# test_board.net
KiCad netlist of a schematic drawn in EAGLE
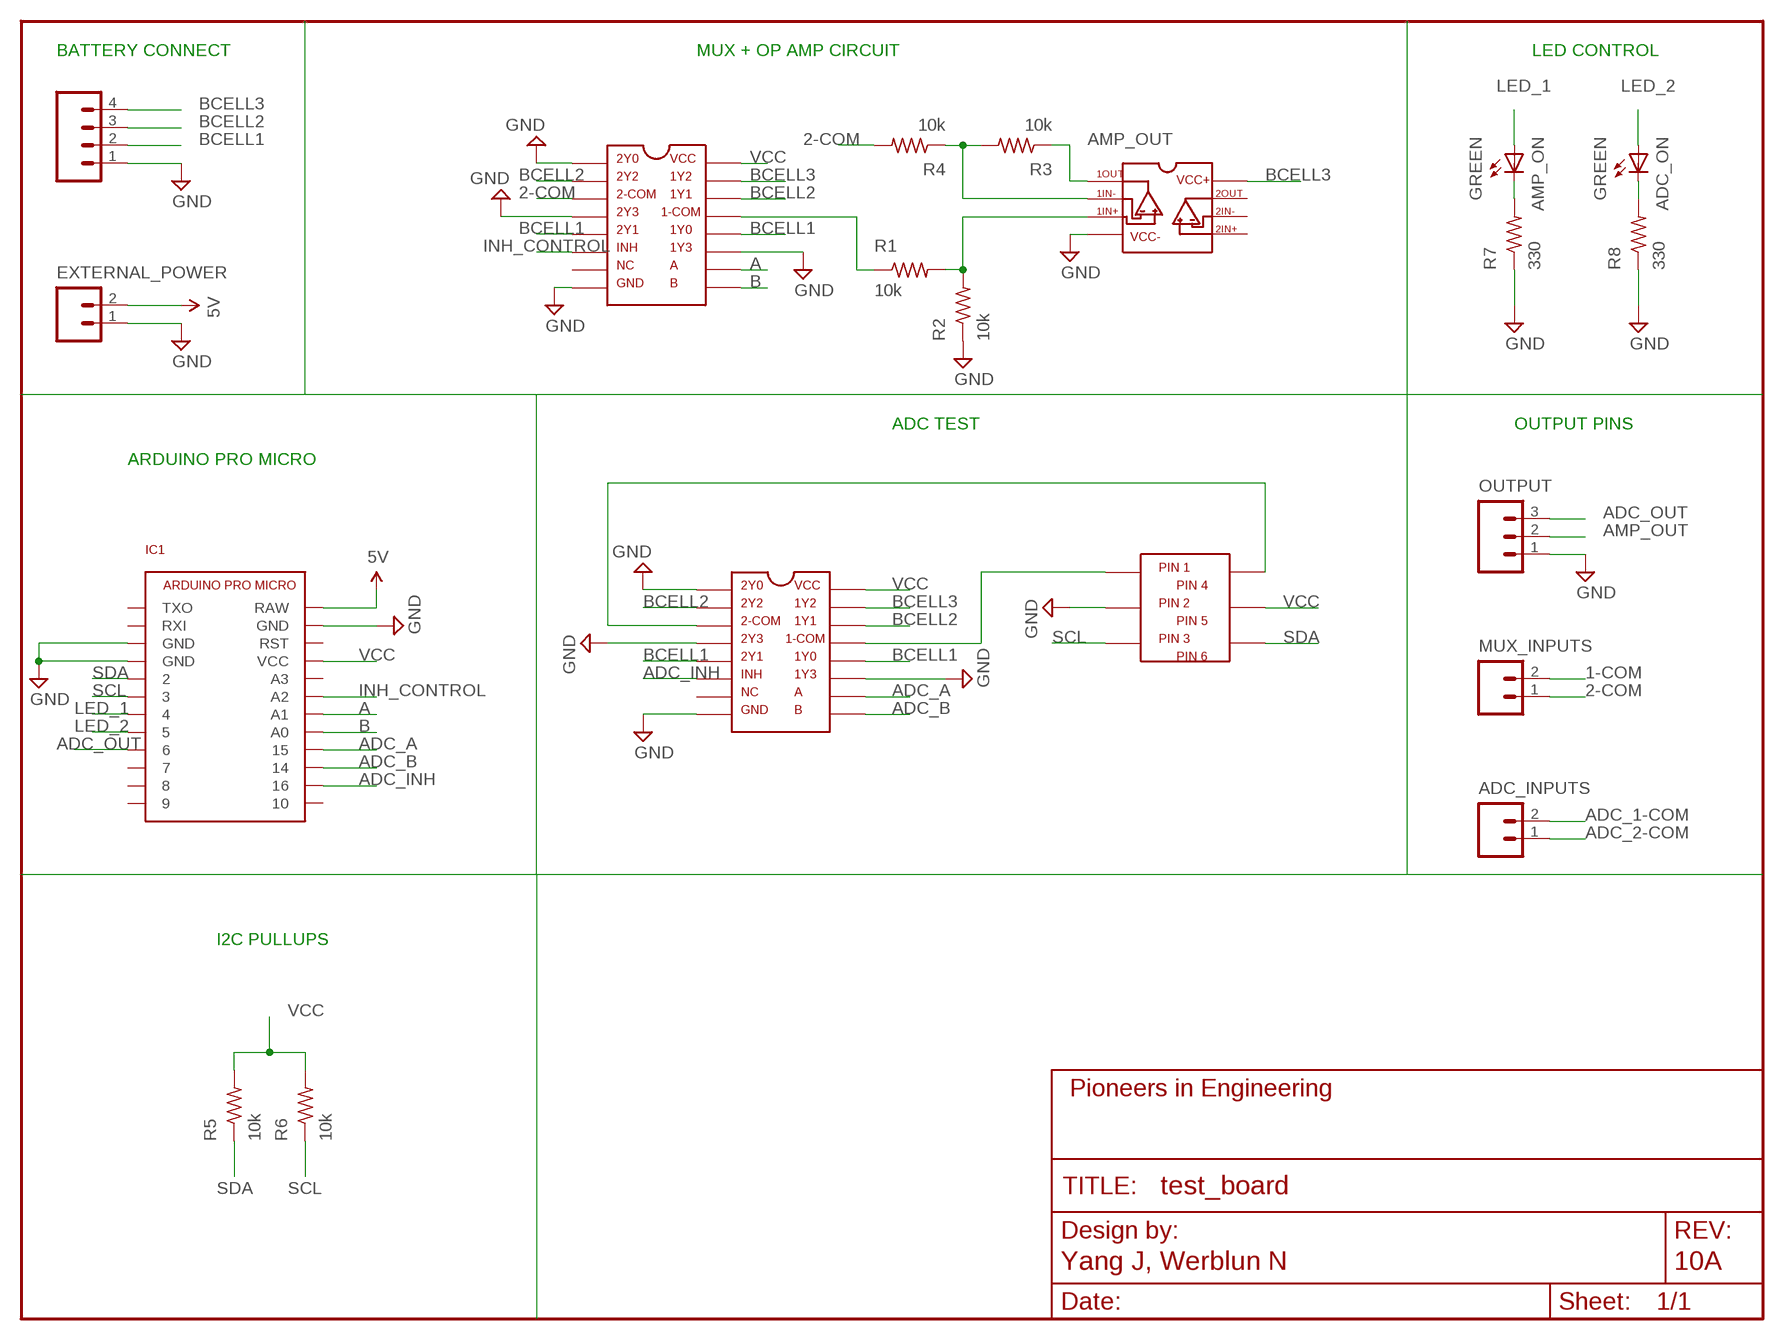
[diagram p0: schematic, sheet 1]

(export (version "E")
  (design (tool "Eeschema 10.0.6"))
  (components
    (comp (ref "ADC_INPUTS")
      (value "M02PTH")
      (footprint "eagle-import:1X02")
      (libsource (lib "eagle-import") (part "M02PTH"))
    )
    (comp (ref "ADC_ON")
      (value "GREEN")
      (footprint "eagle-import:LED-0603")
      (fields
        (field (name "DISTRIBUTOR_PART_NUMBER") "160-1415-1-ND")
        (field (name "MANUFACTURER") "Lite-On Inc")
        (field (name "MANUFACTURER_PART_NUMBER") "LTST-C170KRKT")
      )
      (libsource (lib "eagle-import") (part "LED0603"))
    )
    (comp (ref "AMP_ON")
      (value "GREEN")
      (footprint "eagle-import:LED-0603")
      (fields
        (field (name "DISTRIBUTOR_PART_NUMBER") "160-1415-1-ND")
        (field (name "MANUFACTURER") "Lite-On Inc")
        (field (name "MANUFACTURER_PART_NUMBER") "LTST-C170KRKT")
      )
      (libsource (lib "eagle-import") (part "LED0603"))
    )
    (comp (ref "BATTERY_CONNECT")
      (value "XH_CONNECTOR_4POS")
      (footprint "eagle-import:XH_CONNECTOR_4POS_2.5MM")
      (libsource (lib "eagle-import") (part "XH_CONNECTOR_4POS"))
    )
    (comp (ref "EXTERNAL_POWER")
      (value "M02PTH")
      (footprint "eagle-import:1X02")
      (libsource (lib "eagle-import") (part "M02PTH"))
    )
    (comp (ref "IC1")
      (value "ARDUINO_PRO_MICRO")
      (footprint "eagle-import:ARDUINO_PRO_MICRO")
      (fields
        (field (name "DISTRIBUTOR_PART_NUMBER") "32284746884")
        (field (name "MANUFACTURER") "Feiyang electronics")
      )
      (libsource (lib "eagle-import") (part "ARDUINO_PRO_MICRO"))
    )
    (comp (ref "MUX_INPUTS")
      (value "M02PTH")
      (footprint "eagle-import:1X02")
      (libsource (lib "eagle-import") (part "M02PTH"))
    )
    (comp (ref "OUTPUT")
      (value "M03PTH")
      (footprint "eagle-import:1X03")
      (libsource (lib "eagle-import") (part "M03PTH"))
    )
    (comp (ref "R1")
      (value "10k")
      (footprint "eagle-import:R0603")
      (fields (field (name "MANUFACTURER") "Rohm Semiconductor"))
      (libsource (lib "eagle-import") (part "R-US_R0603"))
    )
    (comp (ref "R2")
      (value "10k")
      (footprint "eagle-import:R0603")
      (fields (field (name "MANUFACTURER") "Rohm Semiconductor"))
      (libsource (lib "eagle-import") (part "R-US_R0603"))
    )
    (comp (ref "R3")
      (value "10k")
      (footprint "eagle-import:R0603")
      (fields (field (name "MANUFACTURER") "Rohm Semiconductor"))
      (libsource (lib "eagle-import") (part "R-US_R0603"))
    )
    (comp (ref "R4")
      (value "10k")
      (footprint "eagle-import:R0603")
      (fields (field (name "MANUFACTURER") "Rohm Semiconductor"))
      (libsource (lib "eagle-import") (part "R-US_R0603"))
    )
    (comp (ref "R5")
      (value "10k")
      (footprint "eagle-import:R0603")
      (fields (field (name "MANUFACTURER") "Rohm Semiconductor"))
      (libsource (lib "eagle-import") (part "R-US_R0603"))
    )
    (comp (ref "R6")
      (value "10k")
      (footprint "eagle-import:R0603")
      (fields (field (name "MANUFACTURER") "Rohm Semiconductor"))
      (libsource (lib "eagle-import") (part "R-US_R0603"))
    )
    (comp (ref "R7")
      (value "330")
      (footprint "eagle-import:R0603")
      (fields (field (name "MANUFACTURER") "Rohm Semiconductor"))
      (libsource (lib "eagle-import") (part "R-US_R0603"))
    )
    (comp (ref "R8")
      (value "330")
      (footprint "eagle-import:R0603")
      (fields (field (name "MANUFACTURER") "Rohm Semiconductor"))
      (libsource (lib "eagle-import") (part "R-US_R0603"))
    )
    (comp (ref "U$1")
      (value "SN74HC4852")
      (footprint "eagle-import:DIL16")
      (libsource (lib "eagle-import") (part "SN74HC4852"))
    )
    (comp (ref "U$2")
      (value "TL072")
      (footprint "eagle-import:DIL08")
      (libsource (lib "eagle-import") (part "TL072"))
    )
    (comp (ref "U$3")
      (value "SOT-23_6PIN")
      (footprint "eagle-import:SOT-23_6PIN")
      (libsource (lib "eagle-import") (part "SOT-23_6PIN"))
    )
    (comp (ref "U$5")
      (value "SN74HC4852")
      (footprint "eagle-import:DIL16")
      (libsource (lib "eagle-import") (part "SN74HC4852"))
    )
  )
  (nets
    (net (code "1") (name "/1-COM") (class "Default")
      (node (ref "MUX_INPUTS") (pin "2") (pinfunction "2_2") (pintype "passive"))
      (node (ref "R1") (pin "1") (pinfunction "1_1") (pintype "passive"))
      (node (ref "U$1") (pin "13") (pinfunction "1-COM_13") (pintype "bidirectional"))
    )
    (net (code "2") (name "/2-COM") (class "Default")
      (node (ref "MUX_INPUTS") (pin "1") (pinfunction "1_1") (pintype "passive"))
      (node (ref "R4") (pin "2") (pinfunction "2_2") (pintype "passive"))
      (node (ref "U$1") (pin "3") (pinfunction "2-COM_3") (pintype "bidirectional"))
    )
    (net (code "3") (name "/A") (class "Default")
      (node (ref "IC1") (pin "A1") (pinfunction "A1_A1") (pintype "bidirectional"))
      (node (ref "U$1") (pin "10") (pinfunction "A_10") (pintype "bidirectional"))
    )
    (net (code "4") (name "/ADC_1-COM") (class "Default")
      (node (ref "ADC_INPUTS") (pin "2") (pinfunction "2_2") (pintype "passive"))
      (node (ref "U$3") (pin "P$1") (pinfunction "P$1_P$1") (pintype "bidirectional"))
      (node (ref "U$5") (pin "13") (pinfunction "1-COM_13") (pintype "bidirectional"))
    )
    (net (code "5") (name "/ADC_2-COM") (class "Default")
      (node (ref "ADC_INPUTS") (pin "1") (pinfunction "1_1") (pintype "passive"))
      (node (ref "U$3") (pin "P$4") (pinfunction "P$4_P$4") (pintype "bidirectional"))
      (node (ref "U$5") (pin "3") (pinfunction "2-COM_3") (pintype "bidirectional"))
    )
    (net (code "6") (name "/ADC_A") (class "Default")
      (node (ref "IC1") (pin "15") (pinfunction "15_15") (pintype "bidirectional"))
      (node (ref "U$5") (pin "10") (pinfunction "A_10") (pintype "bidirectional"))
    )
    (net (code "7") (name "/ADC_B") (class "Default")
      (node (ref "IC1") (pin "14") (pinfunction "14_14") (pintype "bidirectional"))
      (node (ref "U$5") (pin "9") (pinfunction "B_9") (pintype "bidirectional"))
    )
    (net (code "8") (name "/ADC_INH") (class "Default")
      (node (ref "IC1") (pin "16") (pinfunction "16_16") (pintype "bidirectional"))
      (node (ref "U$5") (pin "6") (pinfunction "INH_6") (pintype "bidirectional"))
    )
    (net (code "9") (name "/ADC_OUT") (class "Default")
      (node (ref "IC1") (pin "6") (pinfunction "6_6") (pintype "bidirectional"))
      (node (ref "OUTPUT") (pin "3") (pinfunction "3_3") (pintype "passive"))
    )
    (net (code "10") (name "/AMP_OUT") (class "Default")
      (node (ref "OUTPUT") (pin "2") (pinfunction "2_2") (pintype "passive"))
      (node (ref "R3") (pin "1") (pinfunction "1_1") (pintype "passive"))
      (node (ref "U$2") (pin "1") (pinfunction "1OUT_1") (pintype "bidirectional"))
    )
    (net (code "11") (name "/B") (class "Default")
      (node (ref "IC1") (pin "A0") (pinfunction "A0_A0") (pintype "bidirectional"))
      (node (ref "U$1") (pin "9") (pinfunction "B_9") (pintype "bidirectional"))
    )
    (net (code "12") (name "/BCELL1") (class "Default")
      (node (ref "BATTERY_CONNECT") (pin "2") (pinfunction "2_2") (pintype "passive"))
      (node (ref "U$1") (pin "12") (pinfunction "1Y0_12") (pintype "bidirectional"))
      (node (ref "U$1") (pin "5") (pinfunction "2Y1_5") (pintype "bidirectional"))
      (node (ref "U$5") (pin "12") (pinfunction "1Y0_12") (pintype "bidirectional"))
      (node (ref "U$5") (pin "5") (pinfunction "2Y1_5") (pintype "bidirectional"))
    )
    (net (code "13") (name "/BCELL2") (class "Default")
      (node (ref "BATTERY_CONNECT") (pin "3") (pinfunction "3_3") (pintype "passive"))
      (node (ref "U$1") (pin "14") (pinfunction "1Y1_14") (pintype "bidirectional"))
      (node (ref "U$1") (pin "2") (pinfunction "2Y2_2") (pintype "bidirectional"))
      (node (ref "U$5") (pin "14") (pinfunction "1Y1_14") (pintype "bidirectional"))
      (node (ref "U$5") (pin "2") (pinfunction "2Y2_2") (pintype "bidirectional"))
    )
    (net (code "14") (name "/BCELL3") (class "Default")
      (node (ref "BATTERY_CONNECT") (pin "4") (pinfunction "4_4") (pintype "passive"))
      (node (ref "U$1") (pin "15") (pinfunction "1Y2_15") (pintype "bidirectional"))
      (node (ref "U$2") (pin "8") (pinfunction "VCC+_8") (pintype "bidirectional"))
      (node (ref "U$5") (pin "15") (pinfunction "1Y2_15") (pintype "bidirectional"))
    )
    (net (code "15") (name "/INH_CONTROL") (class "Default")
      (node (ref "IC1") (pin "A2") (pinfunction "A2_A2") (pintype "bidirectional"))
      (node (ref "U$1") (pin "6") (pinfunction "INH_6") (pintype "bidirectional"))
    )
    (net (code "16") (name "/LED_1") (class "Default")
      (node (ref "AMP_ON") (pin "A") (pinfunction "A_A") (pintype "passive"))
      (node (ref "IC1") (pin "4") (pinfunction "4_4") (pintype "bidirectional"))
    )
    (net (code "17") (name "/LED_2") (class "Default")
      (node (ref "ADC_ON") (pin "A") (pinfunction "A_A") (pintype "passive"))
      (node (ref "IC1") (pin "5") (pinfunction "5_5") (pintype "bidirectional"))
    )
    (net (code "18") (name "/SCL") (class "Default")
      (node (ref "IC1") (pin "3") (pinfunction "3_3") (pintype "bidirectional"))
      (node (ref "R6") (pin "1") (pinfunction "1_1") (pintype "passive"))
      (node (ref "U$3") (pin "P$3") (pinfunction "P$3_P$3") (pintype "bidirectional"))
    )
    (net (code "19") (name "/SDA") (class "Default")
      (node (ref "IC1") (pin "2") (pinfunction "2_2") (pintype "bidirectional"))
      (node (ref "R5") (pin "1") (pinfunction "1_1") (pintype "passive"))
      (node (ref "U$3") (pin "P$6") (pinfunction "P$6_P$6") (pintype "bidirectional"))
    )
    (net (code "20") (name "/VCC") (class "Default")
      (node (ref "IC1") (pin "VCC") (pinfunction "VCC_VCC") (pintype "bidirectional"))
      (node (ref "R5") (pin "2") (pinfunction "2_2") (pintype "passive"))
      (node (ref "R6") (pin "2") (pinfunction "2_2") (pintype "passive"))
      (node (ref "U$1") (pin "16") (pinfunction "VCC_16") (pintype "bidirectional"))
      (node (ref "U$3") (pin "P$5") (pinfunction "P$5_P$5") (pintype "bidirectional"))
      (node (ref "U$5") (pin "16") (pinfunction "VCC_16") (pintype "bidirectional"))
    )
    (net (code "21") (name "5V") (class "Default")
      (node (ref "EXTERNAL_POWER") (pin "2") (pinfunction "2_2") (pintype "passive"))
      (node (ref "IC1") (pin "RAW") (pinfunction "RAW_RAW") (pintype "bidirectional"))
    )
    (net (code "22") (name "GND") (class "Default")
      (node (ref "BATTERY_CONNECT") (pin "1") (pinfunction "1_1") (pintype "passive"))
      (node (ref "EXTERNAL_POWER") (pin "1") (pinfunction "1_1") (pintype "passive"))
      (node (ref "IC1") (pin "GND@0") (pinfunction "GND_GND@0") (pintype "bidirectional"))
      (node (ref "IC1") (pin "GND@1") (pinfunction "GND_GND@1") (pintype "bidirectional"))
      (node (ref "IC1") (pin "GND@2") (pinfunction "GND_GND@2") (pintype "bidirectional"))
      (node (ref "OUTPUT") (pin "1") (pinfunction "1_1") (pintype "passive"))
      (node (ref "R2") (pin "1") (pinfunction "1_1") (pintype "passive"))
      (node (ref "R7") (pin "1") (pinfunction "1_1") (pintype "passive"))
      (node (ref "R8") (pin "1") (pinfunction "1_1") (pintype "passive"))
      (node (ref "U$1") (pin "1") (pinfunction "2Y0_1") (pintype "bidirectional"))
      (node (ref "U$1") (pin "11") (pinfunction "1Y3_11") (pintype "bidirectional"))
      (node (ref "U$1") (pin "4") (pinfunction "2Y3_4") (pintype "bidirectional"))
      (node (ref "U$1") (pin "8") (pinfunction "GND_8") (pintype "bidirectional"))
      (node (ref "U$2") (pin "4") (pinfunction "VCC-_4") (pintype "bidirectional"))
      (node (ref "U$3") (pin "P$2") (pinfunction "P$2_P$2") (pintype "bidirectional"))
      (node (ref "U$5") (pin "1") (pinfunction "2Y0_1") (pintype "bidirectional"))
      (node (ref "U$5") (pin "11") (pinfunction "1Y3_11") (pintype "bidirectional"))
      (node (ref "U$5") (pin "4") (pinfunction "2Y3_4") (pintype "bidirectional"))
      (node (ref "U$5") (pin "8") (pinfunction "GND_8") (pintype "bidirectional"))
    )
    (net (code "23") (name "Net-(ADC_ON-PadC)") (class "Default")
      (node (ref "ADC_ON") (pin "C") (pinfunction "C_C") (pintype "passive"))
      (node (ref "R8") (pin "2") (pinfunction "2_2") (pintype "passive"))
    )
    (net (code "24") (name "Net-(AMP_ON-PadC)") (class "Default")
      (node (ref "AMP_ON") (pin "C") (pinfunction "C_C") (pintype "passive"))
      (node (ref "R7") (pin "2") (pinfunction "2_2") (pintype "passive"))
    )
    (net (code "25") (name "Net-(U$2-1IN+)") (class "Default")
      (node (ref "R1") (pin "2") (pinfunction "2_2") (pintype "passive"))
      (node (ref "R2") (pin "2") (pinfunction "2_2") (pintype "passive"))
      (node (ref "U$2") (pin "3") (pinfunction "1IN+_3") (pintype "bidirectional"))
    )
    (net (code "26") (name "Net-(U$2-1IN-)") (class "Default")
      (node (ref "R3") (pin "2") (pinfunction "2_2") (pintype "passive"))
      (node (ref "R4") (pin "1") (pinfunction "1_1") (pintype "passive"))
      (node (ref "U$2") (pin "2") (pinfunction "1IN-_2") (pintype "bidirectional"))
    )
    (net (code "27") (name "unconnected-(IC1-Pad7)") (class "Default")
      (node (ref "IC1") (pin "7") (pinfunction "7_7") (pintype "bidirectional"))
    )
    (net (code "28") (name "unconnected-(IC1-Pad8)") (class "Default")
      (node (ref "IC1") (pin "8") (pinfunction "8_8") (pintype "bidirectional"))
    )
    (net (code "29") (name "unconnected-(IC1-Pad9)") (class "Default")
      (node (ref "IC1") (pin "9") (pinfunction "9_9") (pintype "bidirectional"))
    )
    (net (code "30") (name "unconnected-(IC1-Pad10)") (class "Default")
      (node (ref "IC1") (pin "10") (pinfunction "10_10") (pintype "bidirectional"))
    )
    (net (code "31") (name "unconnected-(IC1-PadA3)") (class "Default")
      (node (ref "IC1") (pin "A3") (pinfunction "A3_A3") (pintype "bidirectional"))
    )
    (net (code "32") (name "unconnected-(IC1-PadRST)") (class "Default")
      (node (ref "IC1") (pin "RST") (pinfunction "RST_RST") (pintype "bidirectional"))
    )
    (net (code "33") (name "unconnected-(IC1-PadRXI)") (class "Default")
      (node (ref "IC1") (pin "RXI") (pinfunction "RXI_RXI") (pintype "bidirectional"))
    )
    (net (code "34") (name "unconnected-(IC1-PadTXO)") (class "Default")
      (node (ref "IC1") (pin "TXO") (pinfunction "TXO_TXO") (pintype "bidirectional"))
    )
    (net (code "35") (name "unconnected-(U$1-NC-Pad7)") (class "Default")
      (node (ref "U$1") (pin "7") (pinfunction "NC_7") (pintype "bidirectional"))
    )
    (net (code "36") (name "unconnected-(U$2-2IN+-Pad5)") (class "Default")
      (node (ref "U$2") (pin "5") (pinfunction "2IN+_5") (pintype "bidirectional"))
    )
    (net (code "37") (name "unconnected-(U$2-2IN--Pad6)") (class "Default")
      (node (ref "U$2") (pin "6") (pinfunction "2IN-_6") (pintype "bidirectional"))
    )
    (net (code "38") (name "unconnected-(U$2-2OUT-Pad7)") (class "Default")
      (node (ref "U$2") (pin "7") (pinfunction "2OUT_7") (pintype "bidirectional"))
    )
    (net (code "39") (name "unconnected-(U$5-NC-Pad7)") (class "Default")
      (node (ref "U$5") (pin "7") (pinfunction "NC_7") (pintype "bidirectional"))
    )
  )
)
